# Jacks.net
KiCad netlist of a schematic drawn in Altium Designer
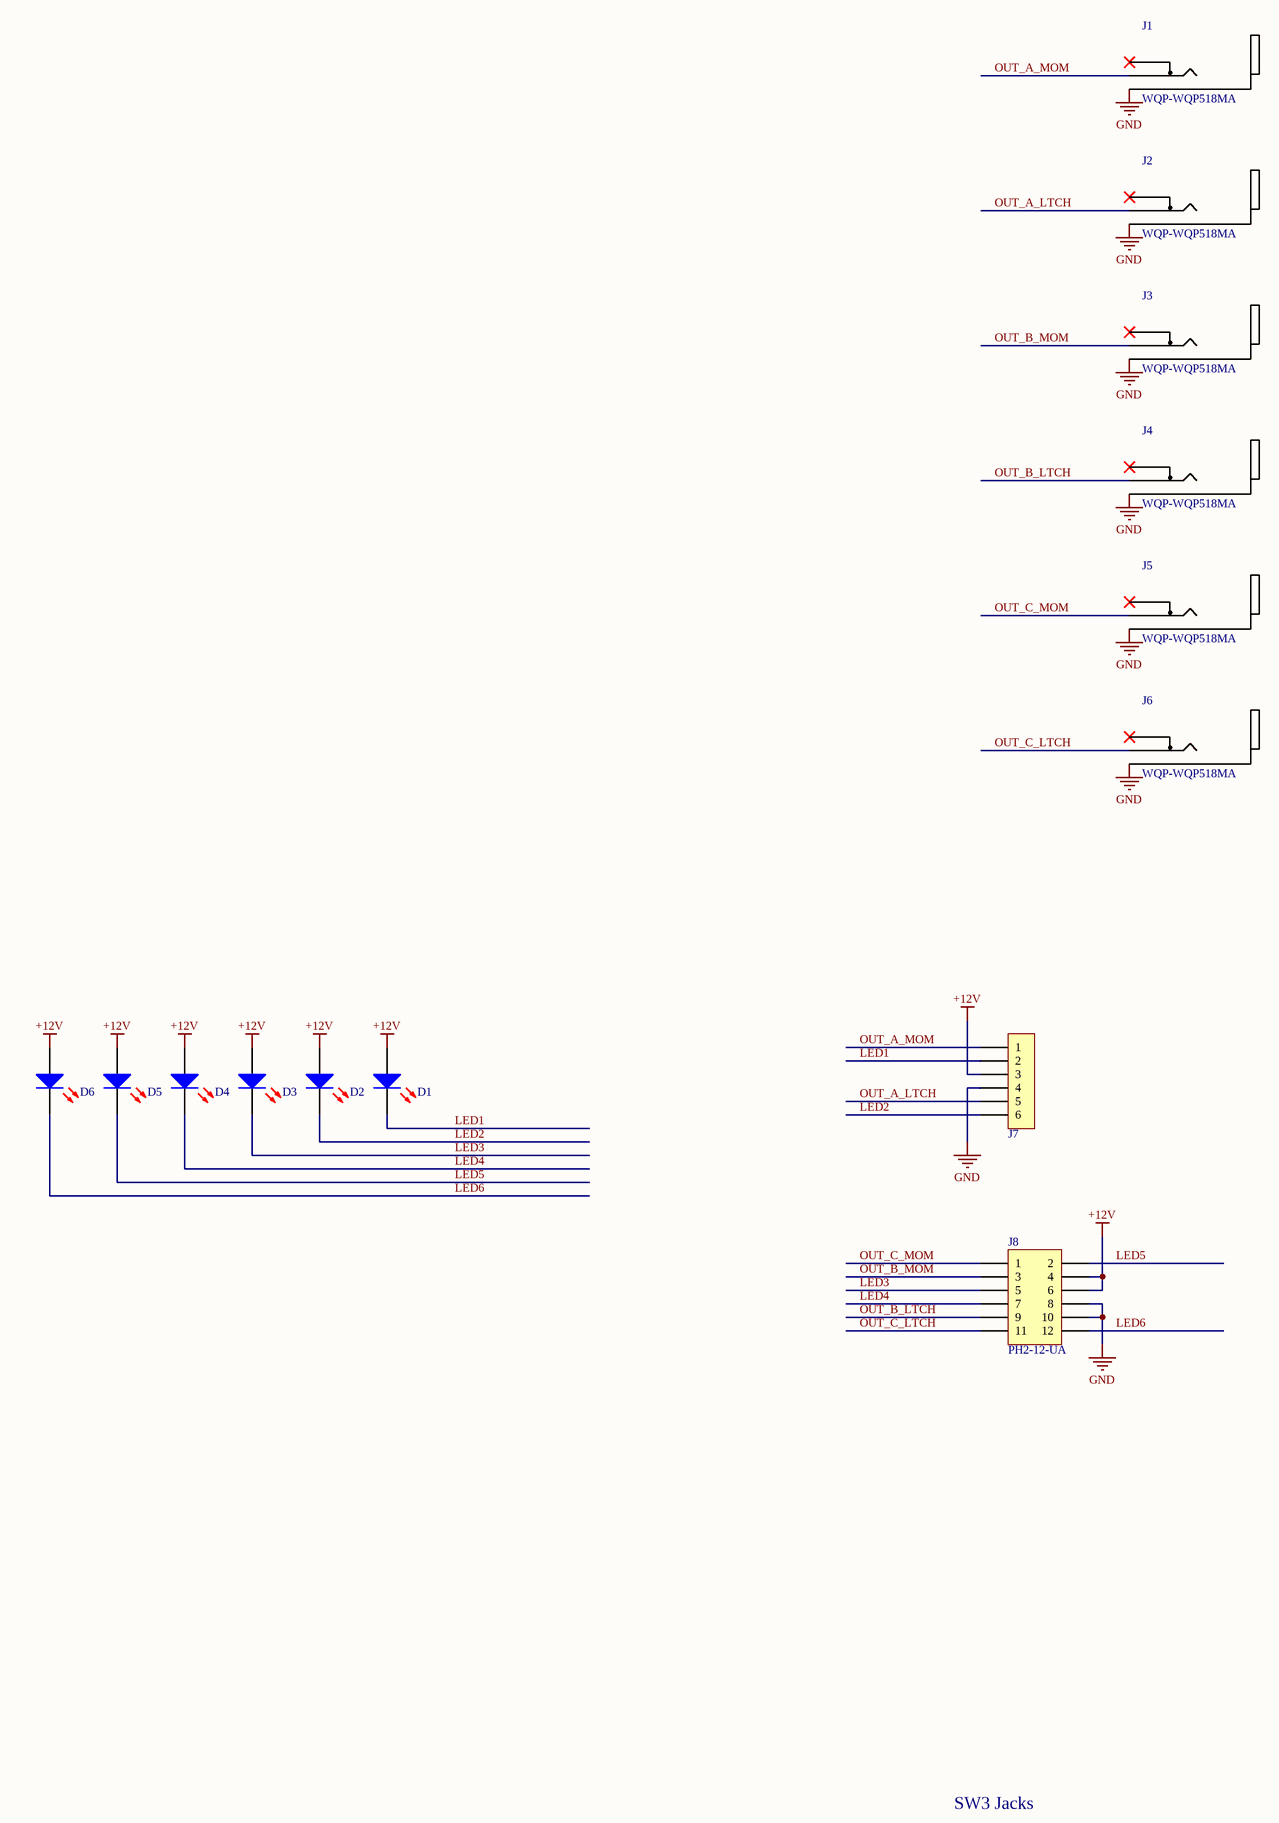
[diagram p0: Jacks.SchDoc]

(export (version "E")
  (design (tool "Eeschema 10.0.6"))
  (components
    (comp (ref "D1")
      (value "RED")
      (footprint "LED_3mm_TH")
      (description "LED RED CLEAR 3MM ROUND T/H")
      (fields (field (name "PARTNUMBER") "151033RS03000") (field (name "MANUFACTURER") "Würth Elektronik"))
      (libsource (lib "Optoelectronics") (part "LED_RED"))
    )
    (comp (ref "D2")
      (value "RED")
      (footprint "LED_3mm_TH")
      (description "LED RED CLEAR 3MM ROUND T/H")
      (fields (field (name "PARTNUMBER") "151033RS03000") (field (name "MANUFACTURER") "Würth Elektronik"))
      (libsource (lib "Optoelectronics") (part "LED_RED"))
    )
    (comp (ref "D3")
      (value "RED")
      (footprint "LED_3mm_TH")
      (description "LED RED CLEAR 3MM ROUND T/H")
      (fields (field (name "PARTNUMBER") "151033RS03000") (field (name "MANUFACTURER") "Würth Elektronik"))
      (libsource (lib "Optoelectronics") (part "LED_RED"))
    )
    (comp (ref "D4")
      (value "RED")
      (footprint "LED_3mm_TH")
      (description "LED RED CLEAR 3MM ROUND T/H")
      (fields (field (name "PARTNUMBER") "151033RS03000") (field (name "MANUFACTURER") "Würth Elektronik"))
      (libsource (lib "Optoelectronics") (part "LED_RED"))
    )
    (comp (ref "D5")
      (value "RED")
      (footprint "LED_3mm_TH")
      (description "LED RED CLEAR 3MM ROUND T/H")
      (fields (field (name "PARTNUMBER") "151033RS03000") (field (name "MANUFACTURER") "Würth Elektronik"))
      (libsource (lib "Optoelectronics") (part "LED_RED"))
    )
    (comp (ref "D6")
      (value "RED")
      (footprint "LED_3mm_TH")
      (description "LED RED CLEAR 3MM ROUND T/H")
      (fields (field (name "PARTNUMBER") "151033RS03000") (field (name "MANUFACTURER") "Würth Elektronik"))
      (libsource (lib "Optoelectronics") (part "LED_RED"))
    )
    (comp (ref "J1")
      (value "WQP-WQP518MA")
      (footprint "PJ301M-12")
      (description "CONN 3.5mm VIRTICAL MONO w/ NORMAL")
      (fields (field (name "MANUFACTURER") "QingPu"))
      (libsource (lib "Connectors") (part "PJ301M-12"))
    )
    (comp (ref "J2")
      (value "WQP-WQP518MA")
      (footprint "PJ301M-12")
      (description "CONN 3.5mm VIRTICAL MONO w/ NORMAL")
      (fields (field (name "MANUFACTURER") "QingPu"))
      (libsource (lib "Connectors") (part "PJ301M-12"))
    )
    (comp (ref "J3")
      (value "WQP-WQP518MA")
      (footprint "PJ301M-12")
      (description "CONN 3.5mm VIRTICAL MONO w/ NORMAL")
      (fields (field (name "MANUFACTURER") "QingPu"))
      (libsource (lib "Connectors") (part "PJ301M-12"))
    )
    (comp (ref "J4")
      (value "WQP-WQP518MA")
      (footprint "PJ301M-12")
      (description "CONN 3.5mm VIRTICAL MONO w/ NORMAL")
      (fields (field (name "MANUFACTURER") "QingPu"))
      (libsource (lib "Connectors") (part "PJ301M-12"))
    )
    (comp (ref "J5")
      (value "WQP-WQP518MA")
      (footprint "PJ301M-12")
      (description "CONN 3.5mm VIRTICAL MONO w/ NORMAL")
      (fields (field (name "MANUFACTURER") "QingPu"))
      (libsource (lib "Connectors") (part "PJ301M-12"))
    )
    (comp (ref "J6")
      (value "WQP-WQP518MA")
      (footprint "PJ301M-12")
      (description "CONN 3.5mm VIRTICAL MONO w/ NORMAL")
      (fields (field (name "MANUFACTURER") "QingPu"))
      (libsource (lib "Connectors") (part "PJ301M-12"))
    )
    (comp (ref "J7")
      (value "PH1-06-UA")
      (footprint "ADAM_TECH_PH1-06-UA")
      (description "CONN HEADER VERT 6POS 2.54MM")
      (fields (field (name "MANUFACTURER") "Adam Tech"))
      (libsource (lib "Connectors") (part "HEADER_1x6"))
    )
    (comp (ref "J8")
      (value "PH2-12-UA")
      (footprint "ADAM_TECH_PH2-12-UA")
      (description "CONN HEADER 12POS DUAL VERT PCB")
      (fields (field (name "MANUFACTURER") "Adam Tech"))
      (libsource (lib "Connectors") (part "HEADER_2x6_ALT"))
    )
  )
  (nets
    (net (code "1") (name "+12V") (class "Default")
      (node (ref "D1") (pin "1") (pinfunction "A_1") (pintype "passive"))
      (node (ref "D2") (pin "1") (pinfunction "A_1") (pintype "passive"))
      (node (ref "D3") (pin "1") (pinfunction "A_1") (pintype "passive"))
      (node (ref "D4") (pin "1") (pinfunction "A_1") (pintype "passive"))
      (node (ref "D5") (pin "1") (pinfunction "A_1") (pintype "passive"))
      (node (ref "D6") (pin "1") (pinfunction "A_1") (pintype "passive"))
      (node (ref "J7") (pin "3") (pinfunction "3_3") (pintype "passive"))
      (node (ref "J8") (pin "4") (pinfunction "4_4") (pintype "passive"))
      (node (ref "J8") (pin "6") (pinfunction "6_6") (pintype "passive"))
    )
    (net (code "2") (name "/LED1") (class "Default")
      (node (ref "D1") (pin "2") (pinfunction "C_2") (pintype "passive"))
      (node (ref "J7") (pin "2") (pinfunction "2_2") (pintype "passive"))
    )
    (net (code "3") (name "/LED2") (class "Default")
      (node (ref "D2") (pin "2") (pinfunction "C_2") (pintype "passive"))
      (node (ref "J7") (pin "6") (pinfunction "6_6") (pintype "passive"))
    )
    (net (code "4") (name "/LED3") (class "Default")
      (node (ref "D3") (pin "2") (pinfunction "C_2") (pintype "passive"))
      (node (ref "J8") (pin "5") (pinfunction "5_5") (pintype "passive"))
    )
    (net (code "5") (name "/LED4") (class "Default")
      (node (ref "D4") (pin "2") (pinfunction "C_2") (pintype "passive"))
      (node (ref "J8") (pin "7") (pinfunction "7_7") (pintype "passive"))
    )
    (net (code "6") (name "/LED5") (class "Default")
      (node (ref "D5") (pin "2") (pinfunction "C_2") (pintype "passive"))
      (node (ref "J8") (pin "2") (pinfunction "2_2") (pintype "passive"))
    )
    (net (code "7") (name "/LED6") (class "Default")
      (node (ref "D6") (pin "2") (pinfunction "C_2") (pintype "passive"))
      (node (ref "J8") (pin "12") (pinfunction "12_12") (pintype "passive"))
    )
    (net (code "8") (name "/OUT_A_LTCH") (class "Default")
      (node (ref "J2") (pin "3") (pinfunction "3_3") (pintype "passive"))
      (node (ref "J7") (pin "5") (pinfunction "5_5") (pintype "passive"))
    )
    (net (code "9") (name "/OUT_A_MOM") (class "Default")
      (node (ref "J1") (pin "3") (pinfunction "3_3") (pintype "passive"))
      (node (ref "J7") (pin "1") (pinfunction "1_1") (pintype "passive"))
    )
    (net (code "10") (name "/OUT_B_LTCH") (class "Default")
      (node (ref "J4") (pin "3") (pinfunction "3_3") (pintype "passive"))
      (node (ref "J8") (pin "9") (pinfunction "9_9") (pintype "passive"))
    )
    (net (code "11") (name "/OUT_B_MOM") (class "Default")
      (node (ref "J3") (pin "3") (pinfunction "3_3") (pintype "passive"))
      (node (ref "J8") (pin "3") (pinfunction "3_3") (pintype "passive"))
    )
    (net (code "12") (name "/OUT_C_LTCH") (class "Default")
      (node (ref "J6") (pin "3") (pinfunction "3_3") (pintype "passive"))
      (node (ref "J8") (pin "11") (pinfunction "11_11") (pintype "passive"))
    )
    (net (code "13") (name "/OUT_C_MOM") (class "Default")
      (node (ref "J5") (pin "3") (pinfunction "3_3") (pintype "passive"))
      (node (ref "J8") (pin "1") (pinfunction "1_1") (pintype "passive"))
    )
    (net (code "14") (name "GND") (class "Default")
      (node (ref "J1") (pin "1") (pinfunction "1_1") (pintype "passive"))
      (node (ref "J2") (pin "1") (pinfunction "1_1") (pintype "passive"))
      (node (ref "J3") (pin "1") (pinfunction "1_1") (pintype "passive"))
      (node (ref "J4") (pin "1") (pinfunction "1_1") (pintype "passive"))
      (node (ref "J5") (pin "1") (pinfunction "1_1") (pintype "passive"))
      (node (ref "J6") (pin "1") (pinfunction "1_1") (pintype "passive"))
      (node (ref "J7") (pin "4") (pinfunction "4_4") (pintype "passive"))
      (node (ref "J8") (pin "10") (pinfunction "10_10") (pintype "passive"))
      (node (ref "J8") (pin "8") (pinfunction "8_8") (pintype "passive"))
    )
    (net (code "15") (name "unconnected-(J1-Pad2)") (class "Default")
      (node (ref "J1") (pin "2") (pinfunction "2_2") (pintype "passive+no_connect"))
    )
    (net (code "16") (name "unconnected-(J2-Pad2)") (class "Default")
      (node (ref "J2") (pin "2") (pinfunction "2_2") (pintype "passive+no_connect"))
    )
    (net (code "17") (name "unconnected-(J3-Pad2)") (class "Default")
      (node (ref "J3") (pin "2") (pinfunction "2_2") (pintype "passive+no_connect"))
    )
    (net (code "18") (name "unconnected-(J4-Pad2)") (class "Default")
      (node (ref "J4") (pin "2") (pinfunction "2_2") (pintype "passive+no_connect"))
    )
    (net (code "19") (name "unconnected-(J5-Pad2)") (class "Default")
      (node (ref "J5") (pin "2") (pinfunction "2_2") (pintype "passive+no_connect"))
    )
    (net (code "20") (name "unconnected-(J6-Pad2)") (class "Default")
      (node (ref "J6") (pin "2") (pinfunction "2_2") (pintype "passive+no_connect"))
    )
  )
)
